# S7CAS-PLEIADES-CARTE-MERE_P07_FPGA_1.net
KiCad netlist of a schematic drawn in Altium Designer
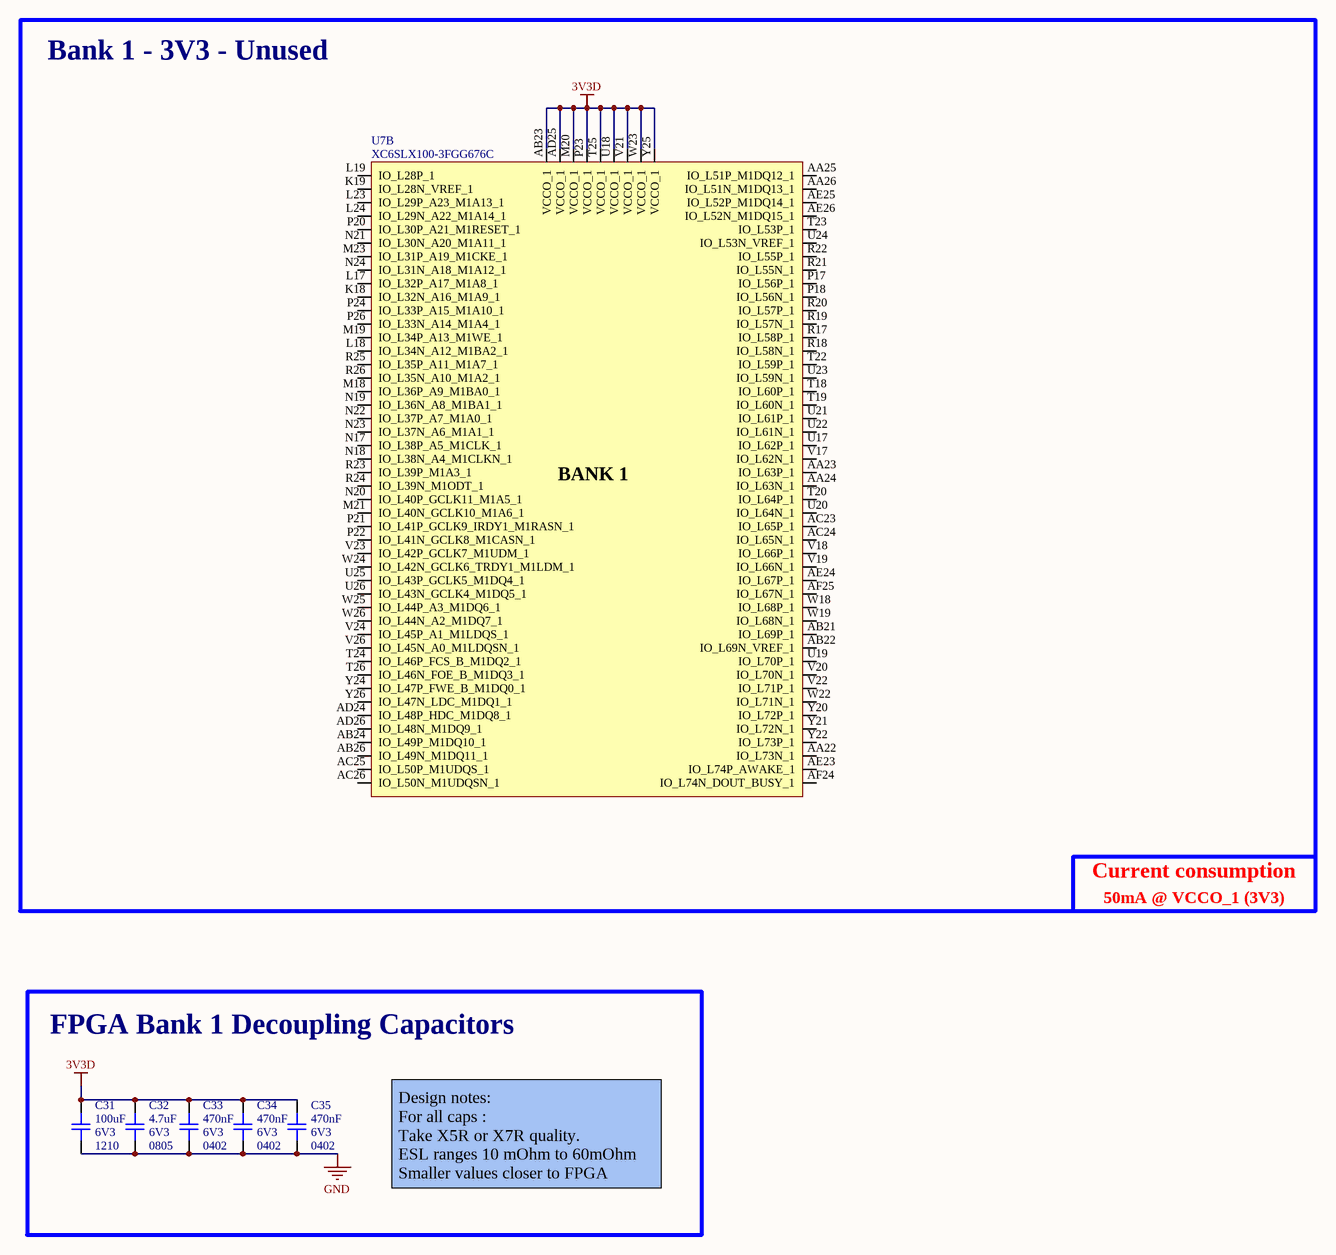
[diagram p0: S7CAS-PLEIADES-CARTE-MERE_P07_FPGA_1.SchDoc]

(export (version "E")
  (design (tool "Eeschema 10.0.6"))
  (components
    (comp (ref "C31")
      (value "100uF")
      (footprint "CAP_1210")
      (description "CAP - 1210")
      (fields
        (field (name "VOLTAGE") "6V3")
        (field (name "PACKAGE") "1210")
        (field (name "CREATEDBY") "Jonathan Bouchard")
      )
      (libsource (lib "S7CAS_LIB2021") (part "CAP - 1210"))
    )
    (comp (ref "C32")
      (value "4.7uF")
      (footprint "CAP_0805")
      (description "CAP - 0805")
      (fields
        (field (name "VOLTAGE") "6V3")
        (field (name "PACKAGE") "0805")
        (field (name "CREATEDBY") "Jonathan Bouchard")
      )
      (libsource (lib "S7CAS_LIB2021") (part "CAP - 0805"))
    )
    (comp (ref "C33")
      (value "470nF")
      (footprint "CAP_0402")
      (description "CAP - 0402")
      (fields
        (field (name "VOLTAGE") "6V3")
        (field (name "PACKAGE") "0402")
        (field (name "CREATEDBY") "Jonathan Bouchard")
      )
      (libsource (lib "S7CAS_LIB2021") (part "CAP - 0402"))
    )
    (comp (ref "C34")
      (value "470nF")
      (footprint "CAP_0402")
      (description "CAP - 0402")
      (fields
        (field (name "VOLTAGE") "6V3")
        (field (name "PACKAGE") "0402")
        (field (name "CREATEDBY") "Jonathan Bouchard")
      )
      (libsource (lib "S7CAS_LIB2021") (part "CAP - 0402"))
    )
    (comp (ref "C35")
      (value "470nF")
      (footprint "CAP_0402")
      (description "CAP - 0402")
      (fields
        (field (name "VOLTAGE") "6V3")
        (field (name "PACKAGE") "0402")
        (field (name "CREATEDBY") "Jonathan Bouchard")
      )
      (libsource (lib "S7CAS_LIB2021") (part "CAP - 0402"))
    )
    (comp (ref "U7")
      (value "XC6SLX100-3FGG676C")
      (footprint "FPGA_XILINX_FGG676")
      (description "FPGA - XILINX SPARTAN 6 480 I/O - BGA-676")
      (fields
        (field (name "VOLTAGE") "1.14 V ~ 1.26 V")
        (field (name "MFG") "Xilinx")
        (field (name "CREATEDBY") "Jonathan Bouchard")
      )
      (libsource (lib "S7CAS_LIB2021") (part "FPGA_XC6SLX100-3FGG676C"))
    )
  )
  (nets
    (net (code "1") (name "3V3D") (class "Default")
      (node (ref "C31") (pin "2") (pinfunction "2_2") (pintype "passive"))
      (node (ref "C32") (pin "2") (pinfunction "2_2") (pintype "passive"))
      (node (ref "C33") (pin "2") (pinfunction "2_2") (pintype "passive"))
      (node (ref "C34") (pin "2") (pinfunction "2_2") (pintype "passive"))
      (node (ref "C35") (pin "2") (pinfunction "2_2") (pintype "passive"))
      (node (ref "U7") (pin "AB23") (pinfunction "VCCO_1_AB23") (pintype "passive"))
      (node (ref "U7") (pin "AD25") (pinfunction "VCCO_1_AD25") (pintype "passive"))
      (node (ref "U7") (pin "M20") (pinfunction "VCCO_1_M20") (pintype "passive"))
      (node (ref "U7") (pin "P23") (pinfunction "VCCO_1_P23") (pintype "passive"))
      (node (ref "U7") (pin "T25") (pinfunction "VCCO_1_T25") (pintype "passive"))
      (node (ref "U7") (pin "U18") (pinfunction "VCCO_1_U18") (pintype "passive"))
      (node (ref "U7") (pin "V21") (pinfunction "VCCO_1_V21") (pintype "passive"))
      (node (ref "U7") (pin "W23") (pinfunction "VCCO_1_W23") (pintype "passive"))
      (node (ref "U7") (pin "Y25") (pinfunction "VCCO_1_Y25") (pintype "passive"))
    )
    (net (code "2") (name "GND") (class "Default")
      (node (ref "C31") (pin "1") (pinfunction "1_1") (pintype "passive"))
      (node (ref "C32") (pin "1") (pinfunction "1_1") (pintype "passive"))
      (node (ref "C33") (pin "1") (pinfunction "1_1") (pintype "passive"))
      (node (ref "C34") (pin "1") (pinfunction "1_1") (pintype "passive"))
      (node (ref "C35") (pin "1") (pinfunction "1_1") (pintype "passive"))
    )
    (net (code "3") (name "unconnected-(U7B-IO_L28N_VREF_1-PadK19)") (class "Default")
      (node (ref "U7") (pin "K19") (pinfunction "IO_L28N_VREF_1_K19") (pintype "passive"))
    )
    (net (code "4") (name "unconnected-(U7B-IO_L28P_1-PadL19)") (class "Default")
      (node (ref "U7") (pin "L19") (pinfunction "IO_L28P_1_L19") (pintype "passive"))
    )
    (net (code "5") (name "unconnected-(U7B-IO_L29N_A22_M1A14_1-PadL24)") (class "Default")
      (node (ref "U7") (pin "L24") (pinfunction "IO_L29N_A22_M1A14_1_L24") (pintype "passive"))
    )
    (net (code "6") (name "unconnected-(U7B-IO_L29P_A23_M1A13_1-PadL23)") (class "Default")
      (node (ref "U7") (pin "L23") (pinfunction "IO_L29P_A23_M1A13_1_L23") (pintype "passive"))
    )
    (net (code "7") (name "unconnected-(U7B-IO_L30N_A20_M1A11_1-PadN21)") (class "Default")
      (node (ref "U7") (pin "N21") (pinfunction "IO_L30N_A20_M1A11_1_N21") (pintype "passive"))
    )
    (net (code "8") (name "unconnected-(U7B-IO_L30P_A21_M1RESET_1-PadP20)") (class "Default")
      (node (ref "U7") (pin "P20") (pinfunction "IO_L30P_A21_M1RESET_1_P20") (pintype "passive"))
    )
    (net (code "9") (name "unconnected-(U7B-IO_L31N_A18_M1A12_1-PadN24)") (class "Default")
      (node (ref "U7") (pin "N24") (pinfunction "IO_L31N_A18_M1A12_1_N24") (pintype "passive"))
    )
    (net (code "10") (name "unconnected-(U7B-IO_L31P_A19_M1CKE_1-PadM23)") (class "Default")
      (node (ref "U7") (pin "M23") (pinfunction "IO_L31P_A19_M1CKE_1_M23") (pintype "passive"))
    )
    (net (code "11") (name "unconnected-(U7B-IO_L32N_A16_M1A9_1-PadK18)") (class "Default")
      (node (ref "U7") (pin "K18") (pinfunction "IO_L32N_A16_M1A9_1_K18") (pintype "passive"))
    )
    (net (code "12") (name "unconnected-(U7B-IO_L32P_A17_M1A8_1-PadL17)") (class "Default")
      (node (ref "U7") (pin "L17") (pinfunction "IO_L32P_A17_M1A8_1_L17") (pintype "passive"))
    )
    (net (code "13") (name "unconnected-(U7B-IO_L33N_A14_M1A4_1-PadP26)") (class "Default")
      (node (ref "U7") (pin "P26") (pinfunction "IO_L33N_A14_M1A4_1_P26") (pintype "passive"))
    )
    (net (code "14") (name "unconnected-(U7B-IO_L33P_A15_M1A10_1-PadP24)") (class "Default")
      (node (ref "U7") (pin "P24") (pinfunction "IO_L33P_A15_M1A10_1_P24") (pintype "passive"))
    )
    (net (code "15") (name "unconnected-(U7B-IO_L34N_A12_M1BA2_1-PadL18)") (class "Default")
      (node (ref "U7") (pin "L18") (pinfunction "IO_L34N_A12_M1BA2_1_L18") (pintype "passive"))
    )
    (net (code "16") (name "unconnected-(U7B-IO_L34P_A13_M1WE_1-PadM19)") (class "Default")
      (node (ref "U7") (pin "M19") (pinfunction "IO_L34P_A13_M1WE_1_M19") (pintype "passive"))
    )
    (net (code "17") (name "unconnected-(U7B-IO_L35N_A10_M1A2_1-PadR26)") (class "Default")
      (node (ref "U7") (pin "R26") (pinfunction "IO_L35N_A10_M1A2_1_R26") (pintype "passive"))
    )
    (net (code "18") (name "unconnected-(U7B-IO_L35P_A11_M1A7_1-PadR25)") (class "Default")
      (node (ref "U7") (pin "R25") (pinfunction "IO_L35P_A11_M1A7_1_R25") (pintype "passive"))
    )
    (net (code "19") (name "unconnected-(U7B-IO_L36N_A8_M1BA1_1-PadN19)") (class "Default")
      (node (ref "U7") (pin "N19") (pinfunction "IO_L36N_A8_M1BA1_1_N19") (pintype "passive"))
    )
    (net (code "20") (name "unconnected-(U7B-IO_L36P_A9_M1BA0_1-PadM18)") (class "Default")
      (node (ref "U7") (pin "M18") (pinfunction "IO_L36P_A9_M1BA0_1_M18") (pintype "passive"))
    )
    (net (code "21") (name "unconnected-(U7B-IO_L37N_A6_M1A1_1-PadN23)") (class "Default")
      (node (ref "U7") (pin "N23") (pinfunction "IO_L37N_A6_M1A1_1_N23") (pintype "passive"))
    )
    (net (code "22") (name "unconnected-(U7B-IO_L37P_A7_M1A0_1-PadN22)") (class "Default")
      (node (ref "U7") (pin "N22") (pinfunction "IO_L37P_A7_M1A0_1_N22") (pintype "passive"))
    )
    (net (code "23") (name "unconnected-(U7B-IO_L38N_A4_M1CLKN_1-PadN18)") (class "Default")
      (node (ref "U7") (pin "N18") (pinfunction "IO_L38N_A4_M1CLKN_1_N18") (pintype "passive"))
    )
    (net (code "24") (name "unconnected-(U7B-IO_L38P_A5_M1CLK_1-PadN17)") (class "Default")
      (node (ref "U7") (pin "N17") (pinfunction "IO_L38P_A5_M1CLK_1_N17") (pintype "passive"))
    )
    (net (code "25") (name "unconnected-(U7B-IO_L39N_M1ODT_1-PadR24)") (class "Default")
      (node (ref "U7") (pin "R24") (pinfunction "IO_L39N_M1ODT_1_R24") (pintype "passive"))
    )
    (net (code "26") (name "unconnected-(U7B-IO_L39P_M1A3_1-PadR23)") (class "Default")
      (node (ref "U7") (pin "R23") (pinfunction "IO_L39P_M1A3_1_R23") (pintype "passive"))
    )
    (net (code "27") (name "unconnected-(U7B-IO_L40N_GCLK10_M1A6_1-PadM21)") (class "Default")
      (node (ref "U7") (pin "M21") (pinfunction "IO_L40N_GCLK10_M1A6_1_M21") (pintype "passive"))
    )
    (net (code "28") (name "unconnected-(U7B-IO_L40P_GCLK11_M1A5_1-PadN20)") (class "Default")
      (node (ref "U7") (pin "N20") (pinfunction "IO_L40P_GCLK11_M1A5_1_N20") (pintype "passive"))
    )
    (net (code "29") (name "unconnected-(U7B-IO_L41N_GCLK8_M1CASN_1-PadP22)") (class "Default")
      (node (ref "U7") (pin "P22") (pinfunction "IO_L41N_GCLK8_M1CASN_1_P22") (pintype "passive"))
    )
    (net (code "30") (name "unconnected-(U7B-IO_L41P_GCLK9_IRDY1_M1RASN_1-PadP21)") (class "Default")
      (node (ref "U7") (pin "P21") (pinfunction "IO_L41P_GCLK9_IRDY1_M1RASN_1_P21") (pintype "passive"))
    )
    (net (code "31") (name "unconnected-(U7B-IO_L42N_GCLK6_TRDY1_M1LDM_1-PadW24)") (class "Default")
      (node (ref "U7") (pin "W24") (pinfunction "IO_L42N_GCLK6_TRDY1_M1LDM_1_W24") (pintype "passive"))
    )
    (net (code "32") (name "unconnected-(U7B-IO_L42P_GCLK7_M1UDM_1-PadV23)") (class "Default")
      (node (ref "U7") (pin "V23") (pinfunction "IO_L42P_GCLK7_M1UDM_1_V23") (pintype "passive"))
    )
    (net (code "33") (name "unconnected-(U7B-IO_L43N_GCLK4_M1DQ5_1-PadU26)") (class "Default")
      (node (ref "U7") (pin "U26") (pinfunction "IO_L43N_GCLK4_M1DQ5_1_U26") (pintype "passive"))
    )
    (net (code "34") (name "unconnected-(U7B-IO_L43P_GCLK5_M1DQ4_1-PadU25)") (class "Default")
      (node (ref "U7") (pin "U25") (pinfunction "IO_L43P_GCLK5_M1DQ4_1_U25") (pintype "passive"))
    )
    (net (code "35") (name "unconnected-(U7B-IO_L44N_A2_M1DQ7_1-PadW26)") (class "Default")
      (node (ref "U7") (pin "W26") (pinfunction "IO_L44N_A2_M1DQ7_1_W26") (pintype "passive"))
    )
    (net (code "36") (name "unconnected-(U7B-IO_L44P_A3_M1DQ6_1-PadW25)") (class "Default")
      (node (ref "U7") (pin "W25") (pinfunction "IO_L44P_A3_M1DQ6_1_W25") (pintype "passive"))
    )
    (net (code "37") (name "unconnected-(U7B-IO_L45N_A0_M1LDQSN_1-PadV26)") (class "Default")
      (node (ref "U7") (pin "V26") (pinfunction "IO_L45N_A0_M1LDQSN_1_V26") (pintype "passive"))
    )
    (net (code "38") (name "unconnected-(U7B-IO_L45P_A1_M1LDQS_1-PadV24)") (class "Default")
      (node (ref "U7") (pin "V24") (pinfunction "IO_L45P_A1_M1LDQS_1_V24") (pintype "passive"))
    )
    (net (code "39") (name "unconnected-(U7B-IO_L46N_FOE_B_M1DQ3_1-PadT26)") (class "Default")
      (node (ref "U7") (pin "T26") (pinfunction "IO_L46N_FOE_B_M1DQ3_1_T26") (pintype "passive"))
    )
    (net (code "40") (name "unconnected-(U7B-IO_L46P_FCS_B_M1DQ2_1-PadT24)") (class "Default")
      (node (ref "U7") (pin "T24") (pinfunction "IO_L46P_FCS_B_M1DQ2_1_T24") (pintype "passive"))
    )
    (net (code "41") (name "unconnected-(U7B-IO_L47N_LDC_M1DQ1_1-PadY26)") (class "Default")
      (node (ref "U7") (pin "Y26") (pinfunction "IO_L47N_LDC_M1DQ1_1_Y26") (pintype "passive"))
    )
    (net (code "42") (name "unconnected-(U7B-IO_L47P_FWE_B_M1DQ0_1-PadY24)") (class "Default")
      (node (ref "U7") (pin "Y24") (pinfunction "IO_L47P_FWE_B_M1DQ0_1_Y24") (pintype "passive"))
    )
    (net (code "43") (name "unconnected-(U7B-IO_L48N_M1DQ9_1-PadAD26)") (class "Default")
      (node (ref "U7") (pin "AD26") (pinfunction "IO_L48N_M1DQ9_1_AD26") (pintype "passive"))
    )
    (net (code "44") (name "unconnected-(U7B-IO_L48P_HDC_M1DQ8_1-PadAD24)") (class "Default")
      (node (ref "U7") (pin "AD24") (pinfunction "IO_L48P_HDC_M1DQ8_1_AD24") (pintype "passive"))
    )
    (net (code "45") (name "unconnected-(U7B-IO_L49N_M1DQ11_1-PadAB26)") (class "Default")
      (node (ref "U7") (pin "AB26") (pinfunction "IO_L49N_M1DQ11_1_AB26") (pintype "passive"))
    )
    (net (code "46") (name "unconnected-(U7B-IO_L49P_M1DQ10_1-PadAB24)") (class "Default")
      (node (ref "U7") (pin "AB24") (pinfunction "IO_L49P_M1DQ10_1_AB24") (pintype "passive"))
    )
    (net (code "47") (name "unconnected-(U7B-IO_L50N_M1UDQSN_1-PadAC26)") (class "Default")
      (node (ref "U7") (pin "AC26") (pinfunction "IO_L50N_M1UDQSN_1_AC26") (pintype "passive"))
    )
    (net (code "48") (name "unconnected-(U7B-IO_L50P_M1UDQS_1-PadAC25)") (class "Default")
      (node (ref "U7") (pin "AC25") (pinfunction "IO_L50P_M1UDQS_1_AC25") (pintype "passive"))
    )
    (net (code "49") (name "unconnected-(U7B-IO_L51N_M1DQ13_1-PadAA26)") (class "Default")
      (node (ref "U7") (pin "AA26") (pinfunction "IO_L51N_M1DQ13_1_AA26") (pintype "passive"))
    )
    (net (code "50") (name "unconnected-(U7B-IO_L51P_M1DQ12_1-PadAA25)") (class "Default")
      (node (ref "U7") (pin "AA25") (pinfunction "IO_L51P_M1DQ12_1_AA25") (pintype "passive"))
    )
    (net (code "51") (name "unconnected-(U7B-IO_L52N_M1DQ15_1-PadAE26)") (class "Default")
      (node (ref "U7") (pin "AE26") (pinfunction "IO_L52N_M1DQ15_1_AE26") (pintype "passive"))
    )
    (net (code "52") (name "unconnected-(U7B-IO_L52P_M1DQ14_1-PadAE25)") (class "Default")
      (node (ref "U7") (pin "AE25") (pinfunction "IO_L52P_M1DQ14_1_AE25") (pintype "passive"))
    )
    (net (code "53") (name "unconnected-(U7B-IO_L53N_VREF_1-PadU24)") (class "Default")
      (node (ref "U7") (pin "U24") (pinfunction "IO_L53N_VREF_1_U24") (pintype "passive"))
    )
    (net (code "54") (name "unconnected-(U7B-IO_L53P_1-PadT23)") (class "Default")
      (node (ref "U7") (pin "T23") (pinfunction "IO_L53P_1_T23") (pintype "passive"))
    )
    (net (code "55") (name "unconnected-(U7B-IO_L55N_1-PadR21)") (class "Default")
      (node (ref "U7") (pin "R21") (pinfunction "IO_L55N_1_R21") (pintype "passive"))
    )
    (net (code "56") (name "unconnected-(U7B-IO_L55P_1-PadR22)") (class "Default")
      (node (ref "U7") (pin "R22") (pinfunction "IO_L55P_1_R22") (pintype "passive"))
    )
    (net (code "57") (name "unconnected-(U7B-IO_L56N_1-PadP18)") (class "Default")
      (node (ref "U7") (pin "P18") (pinfunction "IO_L56N_1_P18") (pintype "passive"))
    )
    (net (code "58") (name "unconnected-(U7B-IO_L56P_1-PadP17)") (class "Default")
      (node (ref "U7") (pin "P17") (pinfunction "IO_L56P_1_P17") (pintype "passive"))
    )
    (net (code "59") (name "unconnected-(U7B-IO_L57N_1-PadR19)") (class "Default")
      (node (ref "U7") (pin "R19") (pinfunction "IO_L57N_1_R19") (pintype "passive"))
    )
    (net (code "60") (name "unconnected-(U7B-IO_L57P_1-PadR20)") (class "Default")
      (node (ref "U7") (pin "R20") (pinfunction "IO_L57P_1_R20") (pintype "passive"))
    )
    (net (code "61") (name "unconnected-(U7B-IO_L58N_1-PadR18)") (class "Default")
      (node (ref "U7") (pin "R18") (pinfunction "IO_L58N_1_R18") (pintype "passive"))
    )
    (net (code "62") (name "unconnected-(U7B-IO_L58P_1-PadR17)") (class "Default")
      (node (ref "U7") (pin "R17") (pinfunction "IO_L58P_1_R17") (pintype "passive"))
    )
    (net (code "63") (name "unconnected-(U7B-IO_L59N_1-PadU23)") (class "Default")
      (node (ref "U7") (pin "U23") (pinfunction "IO_L59N_1_U23") (pintype "passive"))
    )
    (net (code "64") (name "unconnected-(U7B-IO_L59P_1-PadT22)") (class "Default")
      (node (ref "U7") (pin "T22") (pinfunction "IO_L59P_1_T22") (pintype "passive"))
    )
    (net (code "65") (name "unconnected-(U7B-IO_L60N_1-PadT19)") (class "Default")
      (node (ref "U7") (pin "T19") (pinfunction "IO_L60N_1_T19") (pintype "passive"))
    )
    (net (code "66") (name "unconnected-(U7B-IO_L60P_1-PadT18)") (class "Default")
      (node (ref "U7") (pin "T18") (pinfunction "IO_L60P_1_T18") (pintype "passive"))
    )
    (net (code "67") (name "unconnected-(U7B-IO_L61N_1-PadU22)") (class "Default")
      (node (ref "U7") (pin "U22") (pinfunction "IO_L61N_1_U22") (pintype "passive"))
    )
    (net (code "68") (name "unconnected-(U7B-IO_L61P_1-PadU21)") (class "Default")
      (node (ref "U7") (pin "U21") (pinfunction "IO_L61P_1_U21") (pintype "passive"))
    )
    (net (code "69") (name "unconnected-(U7B-IO_L62N_1-PadV17)") (class "Default")
      (node (ref "U7") (pin "V17") (pinfunction "IO_L62N_1_V17") (pintype "passive"))
    )
    (net (code "70") (name "unconnected-(U7B-IO_L62P_1-PadU17)") (class "Default")
      (node (ref "U7") (pin "U17") (pinfunction "IO_L62P_1_U17") (pintype "passive"))
    )
    (net (code "71") (name "unconnected-(U7B-IO_L63N_1-PadAA24)") (class "Default")
      (node (ref "U7") (pin "AA24") (pinfunction "IO_L63N_1_AA24") (pintype "passive"))
    )
    (net (code "72") (name "unconnected-(U7B-IO_L63P_1-PadAA23)") (class "Default")
      (node (ref "U7") (pin "AA23") (pinfunction "IO_L63P_1_AA23") (pintype "passive"))
    )
    (net (code "73") (name "unconnected-(U7B-IO_L64N_1-PadU20)") (class "Default")
      (node (ref "U7") (pin "U20") (pinfunction "IO_L64N_1_U20") (pintype "passive"))
    )
    (net (code "74") (name "unconnected-(U7B-IO_L64P_1-PadT20)") (class "Default")
      (node (ref "U7") (pin "T20") (pinfunction "IO_L64P_1_T20") (pintype "passive"))
    )
    (net (code "75") (name "unconnected-(U7B-IO_L65N_1-PadAC24)") (class "Default")
      (node (ref "U7") (pin "AC24") (pinfunction "IO_L65N_1_AC24") (pintype "passive"))
    )
    (net (code "76") (name "unconnected-(U7B-IO_L65P_1-PadAC23)") (class "Default")
      (node (ref "U7") (pin "AC23") (pinfunction "IO_L65P_1_AC23") (pintype "passive"))
    )
    (net (code "77") (name "unconnected-(U7B-IO_L66N_1-PadV19)") (class "Default")
      (node (ref "U7") (pin "V19") (pinfunction "IO_L66N_1_V19") (pintype "passive"))
    )
    (net (code "78") (name "unconnected-(U7B-IO_L66P_1-PadV18)") (class "Default")
      (node (ref "U7") (pin "V18") (pinfunction "IO_L66P_1_V18") (pintype "passive"))
    )
    (net (code "79") (name "unconnected-(U7B-IO_L67N_1-PadAF25)") (class "Default")
      (node (ref "U7") (pin "AF25") (pinfunction "IO_L67N_1_AF25") (pintype "passive"))
    )
    (net (code "80") (name "unconnected-(U7B-IO_L67P_1-PadAE24)") (class "Default")
      (node (ref "U7") (pin "AE24") (pinfunction "IO_L67P_1_AE24") (pintype "passive"))
    )
    (net (code "81") (name "unconnected-(U7B-IO_L68N_1-PadW19)") (class "Default")
      (node (ref "U7") (pin "W19") (pinfunction "IO_L68N_1_W19") (pintype "passive"))
    )
    (net (code "82") (name "unconnected-(U7B-IO_L68P_1-PadW18)") (class "Default")
      (node (ref "U7") (pin "W18") (pinfunction "IO_L68P_1_W18") (pintype "passive"))
    )
    (net (code "83") (name "unconnected-(U7B-IO_L69N_VREF_1-PadAB22)") (class "Default")
      (node (ref "U7") (pin "AB22") (pinfunction "IO_L69N_VREF_1_AB22") (pintype "passive"))
    )
    (net (code "84") (name "unconnected-(U7B-IO_L69P_1-PadAB21)") (class "Default")
      (node (ref "U7") (pin "AB21") (pinfunction "IO_L69P_1_AB21") (pintype "passive"))
    )
    (net (code "85") (name "unconnected-(U7B-IO_L70N_1-PadV20)") (class "Default")
      (node (ref "U7") (pin "V20") (pinfunction "IO_L70N_1_V20") (pintype "passive"))
    )
    (net (code "86") (name "unconnected-(U7B-IO_L70P_1-PadU19)") (class "Default")
      (node (ref "U7") (pin "U19") (pinfunction "IO_L70P_1_U19") (pintype "passive"))
    )
    (net (code "87") (name "unconnected-(U7B-IO_L71N_1-PadW22)") (class "Default")
      (node (ref "U7") (pin "W22") (pinfunction "IO_L71N_1_W22") (pintype "passive"))
    )
    (net (code "88") (name "unconnected-(U7B-IO_L71P_1-PadV22)") (class "Default")
      (node (ref "U7") (pin "V22") (pinfunction "IO_L71P_1_V22") (pintype "passive"))
    )
    (net (code "89") (name "unconnected-(U7B-IO_L72N_1-PadY21)") (class "Default")
      (node (ref "U7") (pin "Y21") (pinfunction "IO_L72N_1_Y21") (pintype "passive"))
    )
    (net (code "90") (name "unconnected-(U7B-IO_L72P_1-PadY20)") (class "Default")
      (node (ref "U7") (pin "Y20") (pinfunction "IO_L72P_1_Y20") (pintype "passive"))
    )
    (net (code "91") (name "unconnected-(U7B-IO_L73N_1-PadAA22)") (class "Default")
      (node (ref "U7") (pin "AA22") (pinfunction "IO_L73N_1_AA22") (pintype "passive"))
    )
    (net (code "92") (name "unconnected-(U7B-IO_L73P_1-PadY22)") (class "Default")
      (node (ref "U7") (pin "Y22") (pinfunction "IO_L73P_1_Y22") (pintype "passive"))
    )
    (net (code "93") (name "unconnected-(U7B-IO_L74N_DOUT_BUSY_1-PadAF24)") (class "Default")
      (node (ref "U7") (pin "AF24") (pinfunction "IO_L74N_DOUT_BUSY_1_AF24") (pintype "passive"))
    )
    (net (code "94") (name "unconnected-(U7B-IO_L74P_AWAKE_1-PadAE23)") (class "Default")
      (node (ref "U7") (pin "AE23") (pinfunction "IO_L74P_AWAKE_1_AE23") (pintype "passive"))
    )
  )
)
